# Mini_Power_Supply.net
KiCad netlist of a schematic drawn in EAGLE
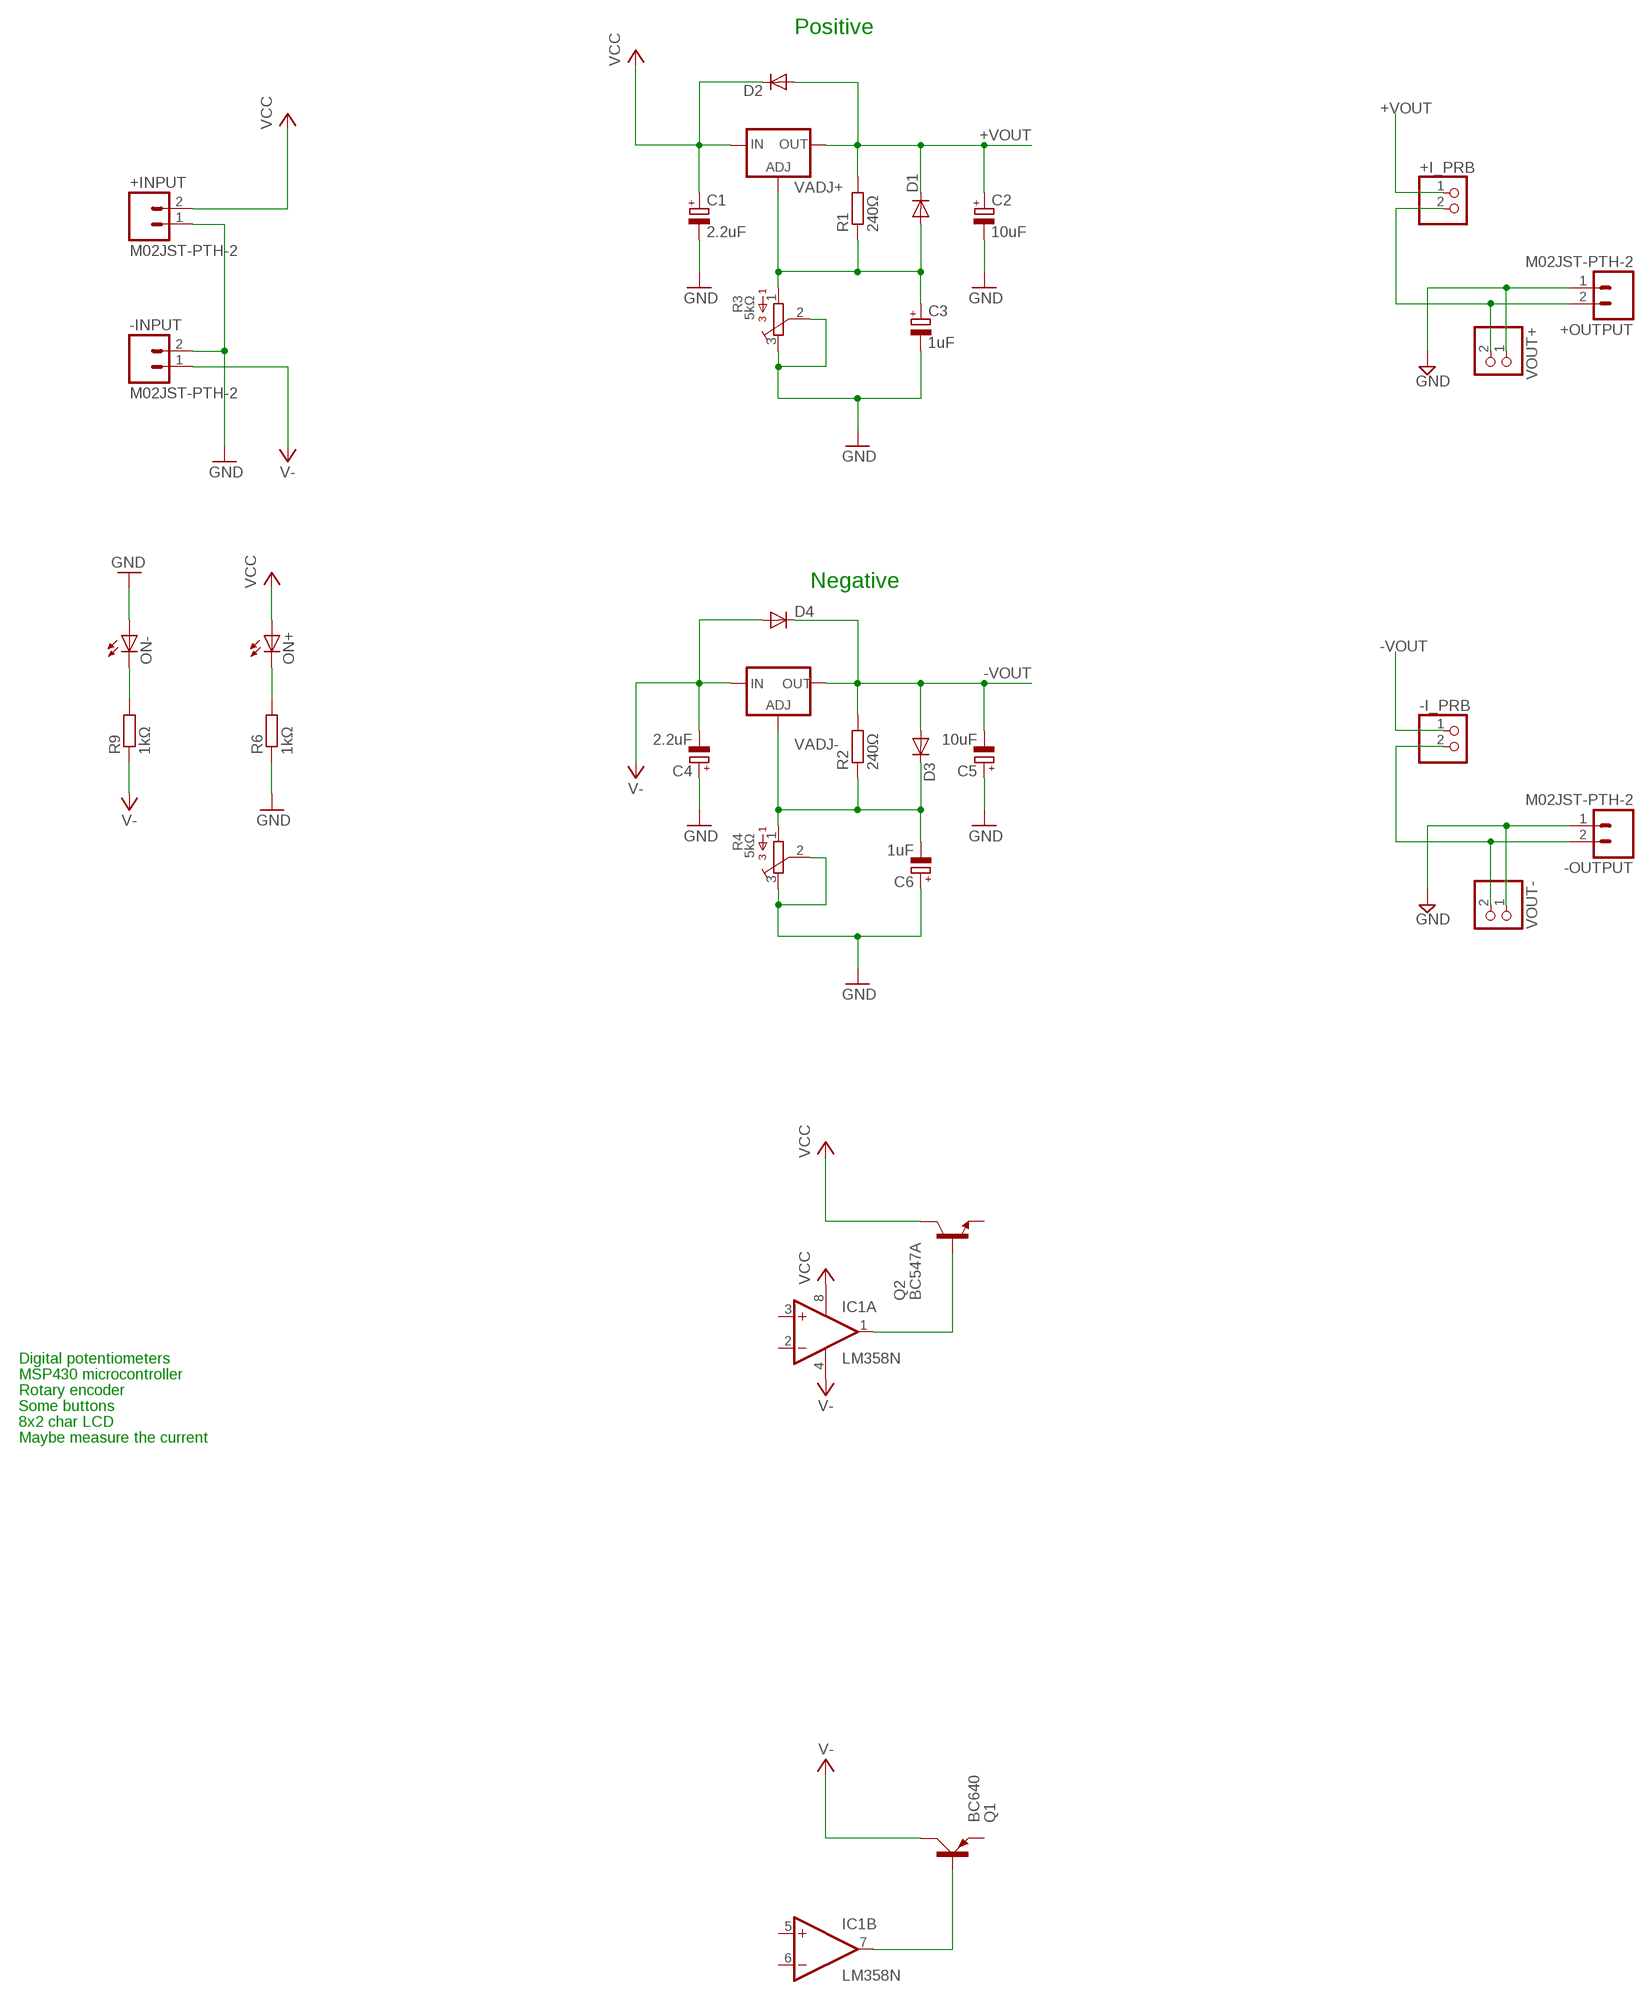
[diagram p0: schematic, sheet 1]

(export (version "E")
  (design (tool "Eeschema 10.0.6"))
  (components
    (comp (ref "+INPUT")
      (value "M02JST-PTH-2")
      (footprint "eagle-import:JST-2-PTH")
      (libsource (lib "eagle-import") (part "M02JST-PTH-2"))
    )
    (comp (ref "+I_PRB")
      (value "PINHD-1X2")
      (footprint "eagle-import:1X02")
      (libsource (lib "eagle-import") (part "PINHD-1X2"))
    )
    (comp (ref "+OUTPUT")
      (value "M02JST-PTH-2")
      (footprint "eagle-import:JST-2-PTH")
      (libsource (lib "eagle-import") (part "M02JST-PTH-2"))
    )
    (comp (ref "-INPUT")
      (value "M02JST-PTH-2")
      (footprint "eagle-import:JST-2-PTH")
      (libsource (lib "eagle-import") (part "M02JST-PTH-2"))
    )
    (comp (ref "-I_PRB")
      (value "PINHD-1X2")
      (footprint "eagle-import:1X02")
      (libsource (lib "eagle-import") (part "PINHD-1X2"))
    )
    (comp (ref "-OUTPUT")
      (value "M02JST-PTH-2")
      (footprint "eagle-import:JST-2-PTH")
      (libsource (lib "eagle-import") (part "M02JST-PTH-2"))
    )
    (comp (ref "C1")
      (value "2.2uF")
      (footprint "eagle-import:E2,5-6")
      (libsource (lib "eagle-import") (part "CPOL-EUE2.5-6"))
    )
    (comp (ref "C2")
      (value "10uF")
      (footprint "eagle-import:E2,5-6")
      (libsource (lib "eagle-import") (part "CPOL-EUE2.5-6"))
    )
    (comp (ref "C3")
      (value "1uF")
      (footprint "eagle-import:E2,5-6")
      (libsource (lib "eagle-import") (part "CPOL-EUE2.5-6"))
    )
    (comp (ref "C4")
      (value "2.2uF")
      (footprint "eagle-import:E2,5-6")
      (libsource (lib "eagle-import") (part "CPOL-EUE2.5-6"))
    )
    (comp (ref "C5")
      (value "10uF")
      (footprint "eagle-import:E2,5-6")
      (libsource (lib "eagle-import") (part "CPOL-EUE2.5-6"))
    )
    (comp (ref "C6")
      (value "1uF")
      (footprint "eagle-import:E2,5-6")
      (libsource (lib "eagle-import") (part "CPOL-EUE2.5-6"))
    )
    (comp (ref "D1")
      (value "1N4148DO35-7")
      (footprint "eagle-import:DO35-7")
      (libsource (lib "eagle-import") (part "1N4148DO35-7"))
    )
    (comp (ref "D2")
      (value "1N4148DO35-7")
      (footprint "eagle-import:DO35-7")
      (libsource (lib "eagle-import") (part "1N4148DO35-7"))
    )
    (comp (ref "D3")
      (value "1N4148DO35-7")
      (footprint "eagle-import:DO35-7")
      (libsource (lib "eagle-import") (part "1N4148DO35-7"))
    )
    (comp (ref "D4")
      (value "1N4148DO35-7")
      (footprint "eagle-import:DO35-7")
      (libsource (lib "eagle-import") (part "1N4148DO35-7"))
    )
    (comp (ref "IC1")
      (value "LM358N")
      (footprint "eagle-import:DIL08")
      (libsource (lib "eagle-import") (part "LM358N"))
    )
    (comp (ref "ON+")
      (value "LEDSQR2X5")
      (footprint "eagle-import:LED2X5")
      (libsource (lib "eagle-import") (part "LEDSQR2X5"))
    )
    (comp (ref "ON-")
      (value "LEDSQR2X5")
      (footprint "eagle-import:LED2X5")
      (libsource (lib "eagle-import") (part "LEDSQR2X5"))
    )
    (comp (ref "Q1")
      (value "BC640")
      (footprint "eagle-import:SOT54D")
      (libsource (lib "eagle-import") (part "BC640"))
    )
    (comp (ref "Q2")
      (value "BC547A")
      (footprint "eagle-import:TO92")
      (libsource (lib "eagle-import") (part "BC547A"))
    )
    (comp (ref "R1")
      (value "240Ω")
      (footprint "eagle-import:0207_10")
      (libsource (lib "eagle-import") (part "R-EU_0207/10"))
    )
    (comp (ref "R2")
      (value "240Ω")
      (footprint "eagle-import:0207_10")
      (libsource (lib "eagle-import") (part "R-EU_0207/10"))
    )
    (comp (ref "R3")
      (value "5kΩ")
      (footprint "eagle-import:3386U")
      (libsource (lib "eagle-import") (part "3386-U"))
    )
    (comp (ref "R4")
      (value "5kΩ")
      (footprint "eagle-import:3386U")
      (libsource (lib "eagle-import") (part "3386-U"))
    )
    (comp (ref "R6")
      (value "1kΩ")
      (footprint "eagle-import:0207_10")
      (libsource (lib "eagle-import") (part "R-EU_0207/10"))
    )
    (comp (ref "R9")
      (value "1kΩ")
      (footprint "eagle-import:0207_10")
      (libsource (lib "eagle-import") (part "R-EU_0207/10"))
    )
    (comp (ref "VADJ+")
      (value "LM317L")
      (footprint "eagle-import:317L")
      (libsource (lib "eagle-import") (part "LM317L"))
    )
    (comp (ref "VADJ-")
      (value "LM337L")
      (footprint "eagle-import:337L")
      (libsource (lib "eagle-import") (part "LM337L"))
    )
    (comp (ref "VOUT+")
      (value "PINHD-1X2")
      (footprint "eagle-import:1X02")
      (libsource (lib "eagle-import") (part "PINHD-1X2"))
    )
    (comp (ref "VOUT-")
      (value "PINHD-1X2")
      (footprint "eagle-import:1X02")
      (libsource (lib "eagle-import") (part "PINHD-1X2"))
    )
  )
  (nets
    (net (code "1") (name "/+VOUT") (class "Default")
      (node (ref "+I_PRB") (pin "1") (pinfunction "1_1") (pintype "passive"))
      (node (ref "C2") (pin "+") (pinfunction "+_+") (pintype "passive"))
      (node (ref "D1") (pin "C") (pinfunction "C_C") (pintype "passive"))
      (node (ref "D2") (pin "A") (pinfunction "A_A") (pintype "passive"))
      (node (ref "R1") (pin "2") (pinfunction "2_2") (pintype "passive"))
      (node (ref "VADJ+") (pin "2") (pinfunction "OUT_2") (pintype "passive"))
    )
    (net (code "2") (name "/-VOUT") (class "Default")
      (node (ref "-I_PRB") (pin "1") (pinfunction "1_1") (pintype "passive"))
      (node (ref "C5") (pin "-") (pinfunction "-_-") (pintype "passive"))
      (node (ref "D3") (pin "A") (pinfunction "A_A") (pintype "passive"))
      (node (ref "D4") (pin "C") (pinfunction "C_C") (pintype "passive"))
      (node (ref "R2") (pin "2") (pinfunction "2_2") (pintype "passive"))
      (node (ref "VADJ-") (pin "OUT") (pinfunction "OUT_OUT") (pintype "passive"))
    )
    (net (code "3") (name "GND") (class "Default")
      (node (ref "+INPUT") (pin "1") (pinfunction "1_1") (pintype "passive"))
      (node (ref "+OUTPUT") (pin "1") (pinfunction "1_1") (pintype "passive"))
      (node (ref "-INPUT") (pin "2") (pinfunction "2_2") (pintype "passive"))
      (node (ref "-OUTPUT") (pin "1") (pinfunction "1_1") (pintype "passive"))
      (node (ref "C1") (pin "-") (pinfunction "-_-") (pintype "passive"))
      (node (ref "C2") (pin "-") (pinfunction "-_-") (pintype "passive"))
      (node (ref "C3") (pin "-") (pinfunction "-_-") (pintype "passive"))
      (node (ref "C4") (pin "+") (pinfunction "+_+") (pintype "passive"))
      (node (ref "C5") (pin "+") (pinfunction "+_+") (pintype "passive"))
      (node (ref "C6") (pin "+") (pinfunction "+_+") (pintype "passive"))
      (node (ref "ON-") (pin "A") (pinfunction "A_A") (pintype "passive"))
      (node (ref "R3") (pin "2") (pinfunction "2_2") (pintype "passive"))
      (node (ref "R3") (pin "3") (pinfunction "3_3") (pintype "passive"))
      (node (ref "R4") (pin "2") (pinfunction "2_2") (pintype "passive"))
      (node (ref "R4") (pin "3") (pinfunction "3_3") (pintype "passive"))
      (node (ref "R6") (pin "1") (pinfunction "1_1") (pintype "passive"))
      (node (ref "VOUT+") (pin "1") (pinfunction "1_1") (pintype "passive"))
      (node (ref "VOUT-") (pin "1") (pinfunction "1_1") (pintype "passive"))
    )
    (net (code "4") (name "Net-(+I_PRB-Pad2)") (class "Default")
      (node (ref "+I_PRB") (pin "2") (pinfunction "2_2") (pintype "passive"))
      (node (ref "+OUTPUT") (pin "2") (pinfunction "2_2") (pintype "passive"))
      (node (ref "VOUT+") (pin "2") (pinfunction "2_2") (pintype "passive"))
    )
    (net (code "5") (name "Net-(-I_PRB-Pad2)") (class "Default")
      (node (ref "-I_PRB") (pin "2") (pinfunction "2_2") (pintype "passive"))
      (node (ref "-OUTPUT") (pin "2") (pinfunction "2_2") (pintype "passive"))
      (node (ref "VOUT-") (pin "2") (pinfunction "2_2") (pintype "passive"))
    )
    (net (code "6") (name "Net-(C6-Pad-)") (class "Default")
      (node (ref "C6") (pin "-") (pinfunction "-_-") (pintype "passive"))
      (node (ref "D3") (pin "C") (pinfunction "C_C") (pintype "passive"))
      (node (ref "R2") (pin "1") (pinfunction "1_1") (pintype "passive"))
      (node (ref "R4") (pin "1") (pinfunction "1_1") (pintype "passive"))
      (node (ref "VADJ-") (pin "ADJ") (pinfunction "ADJ_ADJ") (pintype "input"))
    )
    (net (code "7") (name "Net-(IC1A-OUT)") (class "Default")
      (node (ref "IC1") (pin "1") (pinfunction "OUT_1") (pintype "output"))
      (node (ref "Q2") (pin "2") (pinfunction "B_2") (pintype "passive"))
    )
    (net (code "8") (name "Net-(IC1B-OUT)") (class "Default")
      (node (ref "IC1") (pin "7") (pinfunction "OUT_7") (pintype "output"))
      (node (ref "Q1") (pin "B") (pinfunction "B_B") (pintype "passive"))
    )
    (net (code "9") (name "Net-(ON+-C)") (class "Default")
      (node (ref "ON+") (pin "K") (pinfunction "C_K") (pintype "passive"))
      (node (ref "R6") (pin "2") (pinfunction "2_2") (pintype "passive"))
    )
    (net (code "10") (name "Net-(ON--C)") (class "Default")
      (node (ref "ON-") (pin "K") (pinfunction "C_K") (pintype "passive"))
      (node (ref "R9") (pin "2") (pinfunction "2_2") (pintype "passive"))
    )
    (net (code "11") (name "Net-(VADJ+-ADJ)") (class "Default")
      (node (ref "C3") (pin "+") (pinfunction "+_+") (pintype "passive"))
      (node (ref "D1") (pin "A") (pinfunction "A_A") (pintype "passive"))
      (node (ref "R1") (pin "1") (pinfunction "1_1") (pintype "passive"))
      (node (ref "R3") (pin "1") (pinfunction "1_1") (pintype "passive"))
      (node (ref "VADJ+") (pin "1") (pinfunction "ADJ_1") (pintype "input"))
    )
    (net (code "12") (name "V-") (class "Default")
      (node (ref "-INPUT") (pin "1") (pinfunction "1_1") (pintype "passive"))
      (node (ref "C4") (pin "-") (pinfunction "-_-") (pintype "passive"))
      (node (ref "D4") (pin "A") (pinfunction "A_A") (pintype "passive"))
      (node (ref "IC1") (pin "4") (pinfunction "V-_4") (pintype "power_in"))
      (node (ref "Q1") (pin "C") (pinfunction "C_C") (pintype "passive"))
      (node (ref "R9") (pin "1") (pinfunction "1_1") (pintype "passive"))
      (node (ref "VADJ-") (pin "IN") (pinfunction "IN_IN") (pintype "input"))
    )
    (net (code "13") (name "VCC") (class "Default")
      (node (ref "+INPUT") (pin "2") (pinfunction "2_2") (pintype "passive"))
      (node (ref "C1") (pin "+") (pinfunction "+_+") (pintype "passive"))
      (node (ref "D2") (pin "C") (pinfunction "C_C") (pintype "passive"))
      (node (ref "IC1") (pin "8") (pinfunction "V+_8") (pintype "power_in"))
      (node (ref "ON+") (pin "A") (pinfunction "A_A") (pintype "passive"))
      (node (ref "Q2") (pin "3") (pinfunction "C_3") (pintype "passive"))
      (node (ref "VADJ+") (pin "3") (pinfunction "IN_3") (pintype "input"))
    )
    (net (code "14") (name "unconnected-(IC1A-+IN-Pad3)") (class "Default")
      (node (ref "IC1") (pin "3") (pinfunction "+IN_3") (pintype "input"))
    )
    (net (code "15") (name "unconnected-(IC1A--IN-Pad2)") (class "Default")
      (node (ref "IC1") (pin "2") (pinfunction "-IN_2") (pintype "input"))
    )
    (net (code "16") (name "unconnected-(IC1B-+IN-Pad5)") (class "Default")
      (node (ref "IC1") (pin "5") (pinfunction "+IN_5") (pintype "input"))
    )
    (net (code "17") (name "unconnected-(IC1B--IN-Pad6)") (class "Default")
      (node (ref "IC1") (pin "6") (pinfunction "-IN_6") (pintype "input"))
    )
    (net (code "18") (name "unconnected-(Q1-PadE)") (class "Default")
      (node (ref "Q1") (pin "E") (pinfunction "E_E") (pintype "passive"))
    )
    (net (code "19") (name "unconnected-(Q2-E-Pad1)") (class "Default")
      (node (ref "Q2") (pin "1") (pinfunction "E_1") (pintype "passive"))
    )
  )
)
